# Solenoid_10.net
KiCad netlist of a schematic drawn in EAGLE
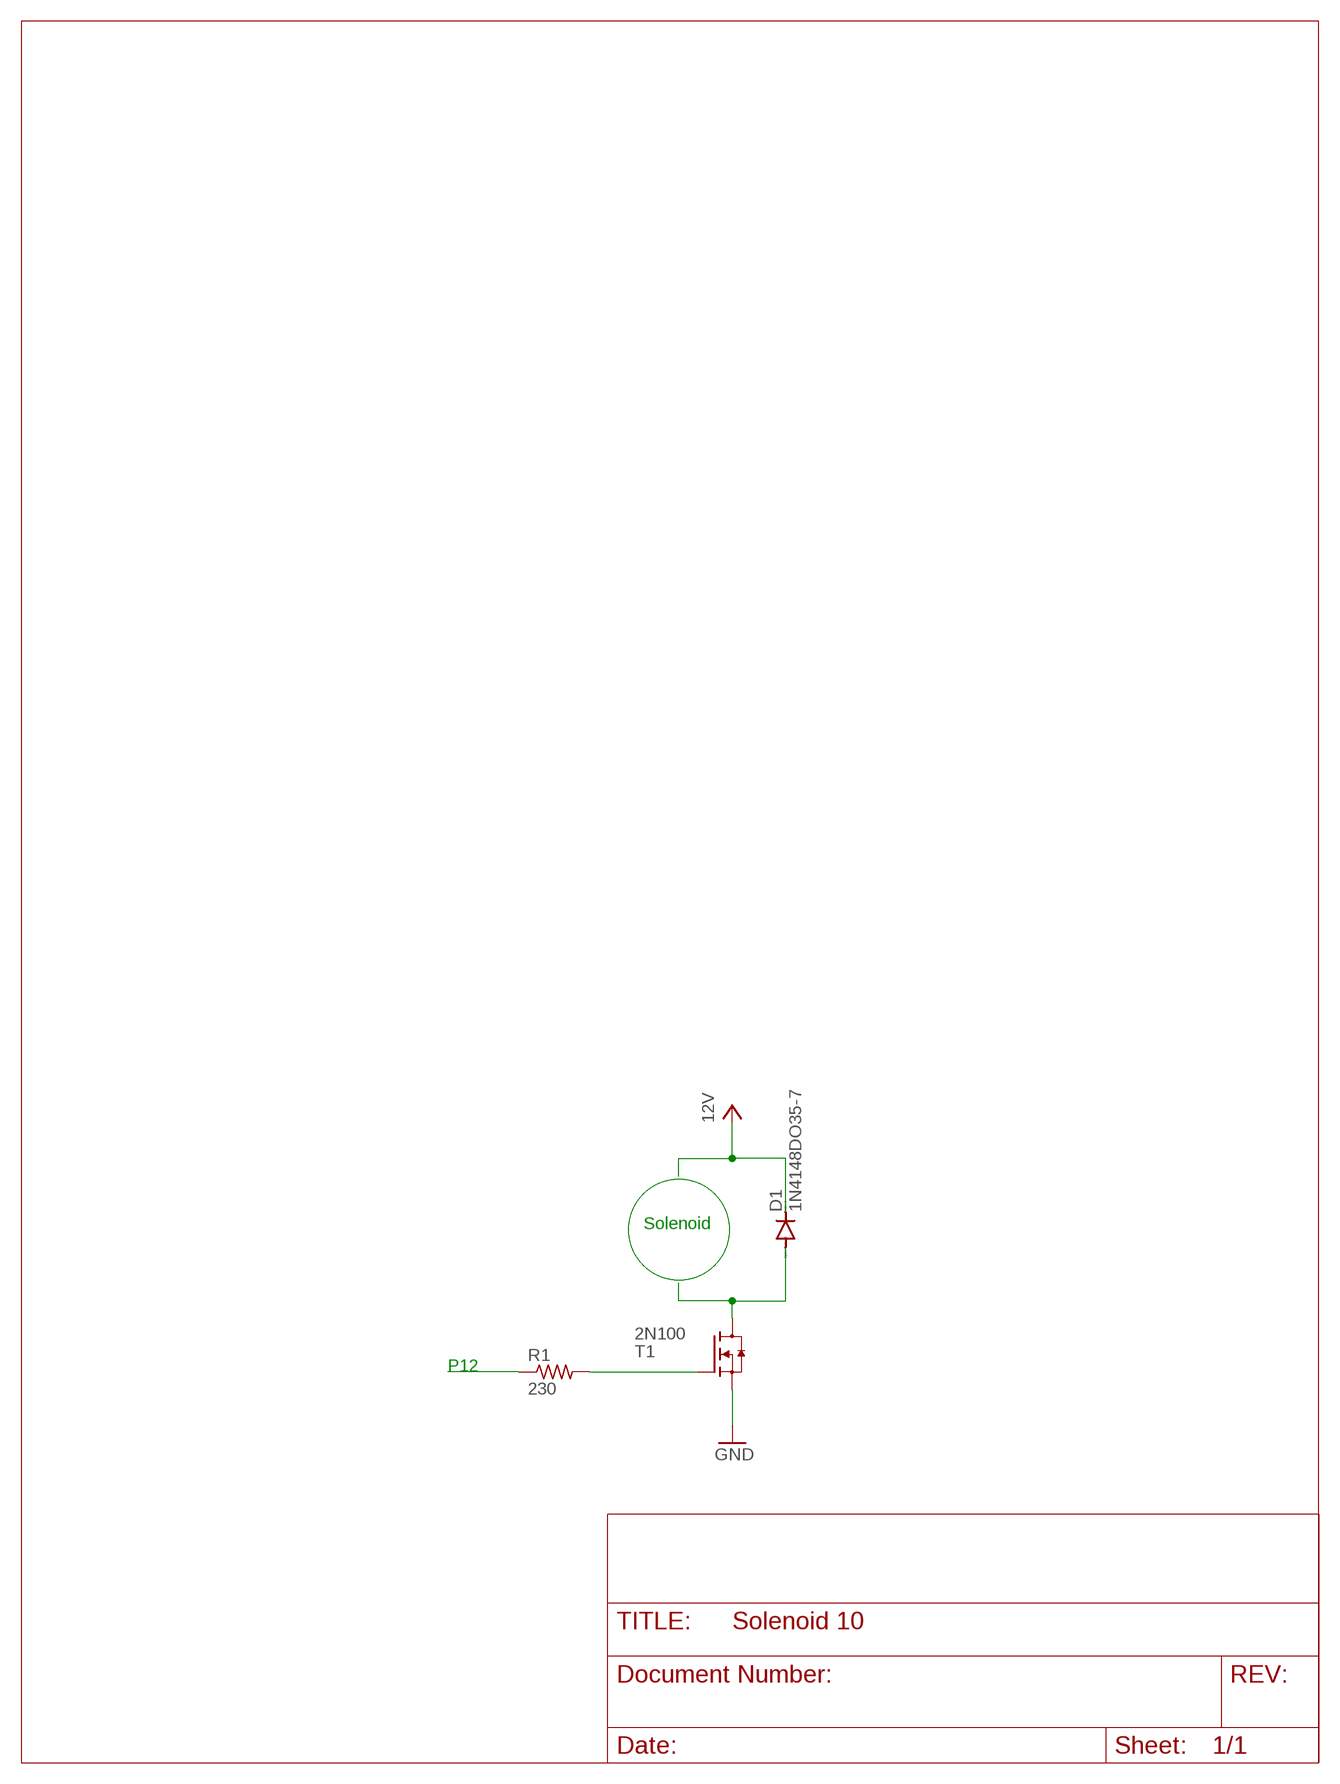
[diagram p0: schematic, sheet 1]

(export (version "E")
  (design (tool "Eeschema 10.0.6"))
  (components
    (comp (ref "D1")
      (value "1N4148DO35-7")
      (footprint "eagle-import:DO35-7")
      (libsource (lib "eagle-import") (part "1N4148DO35-7"))
    )
    (comp (ref "R1")
      (value "230")
      (footprint "eagle-import:0204_7")
      (libsource (lib "eagle-import") (part "R-US_0204/7"))
    )
    (comp (ref "T1")
      (value "2N100")
      (footprint "eagle-import:PG-TO263-7-3")
      (libsource (lib "eagle-import") (part "IPB180N06S4-H1"))
    )
  )
  (nets
    (net (code "1") (name "12V") (class "Default")
      (node (ref "D1") (pin "C") (pinfunction "C_C") (pintype "passive"))
    )
    (net (code "2") (name "GND") (class "Default")
      (node (ref "T1") (pin "2") (pinfunction "S_2") (pintype "passive"))
      (node (ref "T1") (pin "3") (pinfunction "S_3") (pintype "passive"))
      (node (ref "T1") (pin "5") (pinfunction "S_5") (pintype "passive"))
      (node (ref "T1") (pin "6") (pinfunction "S_6") (pintype "passive"))
      (node (ref "T1") (pin "7") (pinfunction "S_7") (pintype "passive"))
    )
    (net (code "3") (name "Net-(T1-D)") (class "Default")
      (node (ref "D1") (pin "A") (pinfunction "A_A") (pintype "passive"))
      (node (ref "T1") (pin "8") (pinfunction "D_8") (pintype "passive"))
    )
    (net (code "4") (name "Net-(T1-G)") (class "Default")
      (node (ref "R1") (pin "2") (pinfunction "2_2") (pintype "passive"))
      (node (ref "T1") (pin "1") (pinfunction "G_1") (pintype "passive"))
    )
    (net (code "5") (name "unconnected-(R1-Pad1)") (class "Default")
      (node (ref "R1") (pin "1") (pinfunction "1_1") (pintype "passive"))
    )
  )
)
